# MPU9150_Breakout.net
KiCad netlist of a schematic drawn in EAGLE
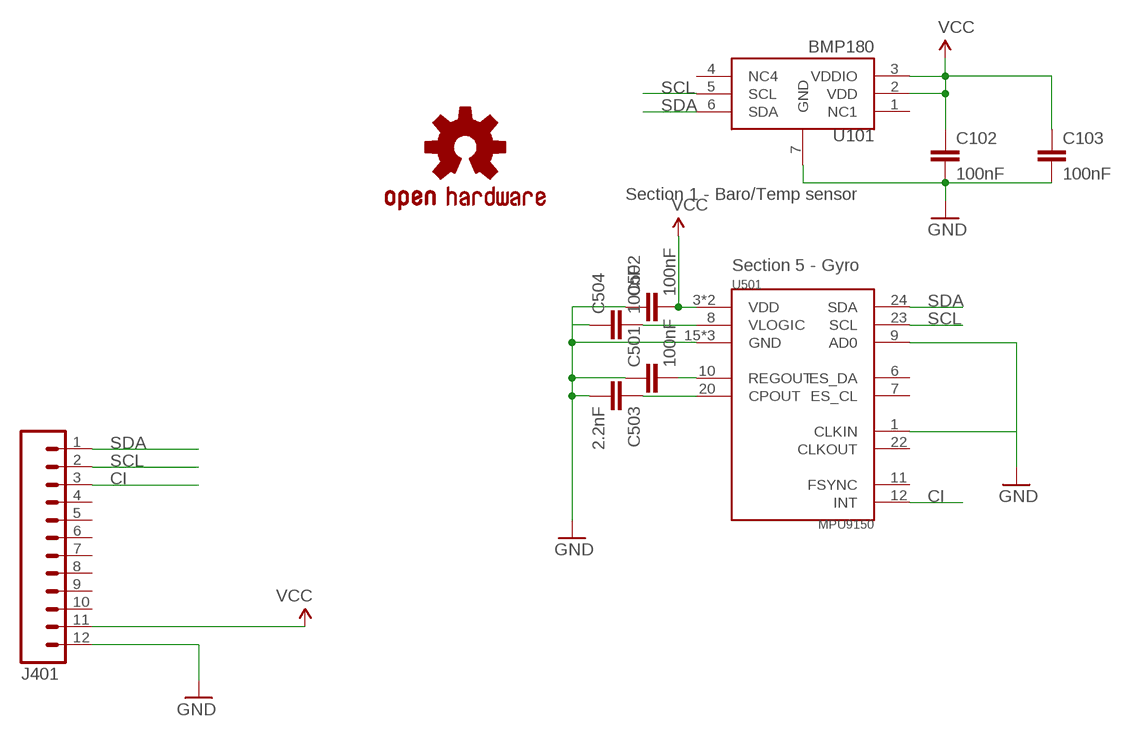
[diagram p0: schematic, sheet 1]

(export (version "E")
  (design (tool "Eeschema 10.0.6"))
  (components
    (comp (ref "C102")
      (value "100nF")
      (footprint "eagle-import:0603-CAP")
      (libsource (lib "eagle-import") (part "CAP0603-CAP"))
    )
    (comp (ref "C103")
      (value "100nF")
      (footprint "eagle-import:0603-CAP")
      (libsource (lib "eagle-import") (part "CAP0603-CAP"))
    )
    (comp (ref "C501")
      (value "100nF")
      (footprint "eagle-import:0603-CAP")
      (libsource (lib "eagle-import") (part "CAP0603-CAP"))
    )
    (comp (ref "C502")
      (value "100nF")
      (footprint "eagle-import:0603-CAP")
      (libsource (lib "eagle-import") (part "CAP0603-CAP"))
    )
    (comp (ref "C503")
      (value "2.2nF")
      (footprint "eagle-import:0603-CAP")
      (libsource (lib "eagle-import") (part "CAP0603-CAP"))
    )
    (comp (ref "C504")
      (value "100nF")
      (footprint "eagle-import:0603-CAP")
      (libsource (lib "eagle-import") (part "CAP0603-CAP"))
    )
    (comp (ref "J401")
      (value "M12PTH")
      (footprint "eagle-import:1X12")
      (libsource (lib "eagle-import") (part "M12PTH"))
    )
    (comp (ref "U$2")
      (value "OSHW-LOGOS")
      (footprint "eagle-import:OSHW-LOGO-S")
      (libsource (lib "eagle-import") (part "OSHW-LOGOS"))
    )
    (comp (ref "U101")
      (value "BMP180")
      (footprint "eagle-import:BMP180")
      (libsource (lib "eagle-import") (part "BMP180"))
    )
    (comp (ref "U501")
      (value "MPU9150")
      (footprint "eagle-import:LLGA24")
      (libsource (lib "eagle-import") (part "MPU9150"))
    )
  )
  (nets
    (net (code "1") (name "/CI") (class "Default")
      (node (ref "J401") (pin "3") (pinfunction "3_3") (pintype "passive"))
      (node (ref "U501") (pin "12") (pinfunction "INT_12") (pintype "bidirectional"))
    )
    (net (code "2") (name "/SCL") (class "Default")
      (node (ref "J401") (pin "2") (pinfunction "2_2") (pintype "passive"))
      (node (ref "U101") (pin "5") (pinfunction "SCL_5") (pintype "input"))
      (node (ref "U501") (pin "23") (pinfunction "SCL_23") (pintype "bidirectional"))
    )
    (net (code "3") (name "/SDA") (class "Default")
      (node (ref "J401") (pin "1") (pinfunction "1_1") (pintype "passive"))
      (node (ref "U101") (pin "6") (pinfunction "SDA_6") (pintype "bidirectional"))
      (node (ref "U501") (pin "24") (pinfunction "SDA_24") (pintype "bidirectional"))
    )
    (net (code "4") (name "GND") (class "Default")
      (node (ref "C102") (pin "2") (pinfunction "2_2") (pintype "passive"))
      (node (ref "C103") (pin "2") (pinfunction "2_2") (pintype "passive"))
      (node (ref "C501") (pin "1") (pinfunction "1_1") (pintype "passive"))
      (node (ref "C502") (pin "1") (pinfunction "1_1") (pintype "passive"))
      (node (ref "C503") (pin "2") (pinfunction "2_2") (pintype "passive"))
      (node (ref "C504") (pin "1") (pinfunction "1_1") (pintype "passive"))
      (node (ref "J401") (pin "12") (pinfunction "12_12") (pintype "passive"))
      (node (ref "U101") (pin "7") (pinfunction "GND_7") (pintype "power_in"))
      (node (ref "U501") (pin "1") (pinfunction "CLKIN_1") (pintype "bidirectional"))
      (node (ref "U501") (pin "15") (pinfunction "GND_15") (pintype "bidirectional"))
      (node (ref "U501") (pin "17") (pinfunction "GND_17") (pintype "bidirectional"))
      (node (ref "U501") (pin "18") (pinfunction "GND_18") (pintype "bidirectional"))
      (node (ref "U501") (pin "9") (pinfunction "AD0_9") (pintype "bidirectional"))
    )
    (net (code "5") (name "Net-(U501-CPOUT)") (class "Default")
      (node (ref "C503") (pin "1") (pinfunction "1_1") (pintype "passive"))
      (node (ref "U501") (pin "20") (pinfunction "CPOUT_20") (pintype "bidirectional"))
    )
    (net (code "6") (name "Net-(U501-REGOUT)") (class "Default")
      (node (ref "C501") (pin "2") (pinfunction "2_2") (pintype "passive"))
      (node (ref "U501") (pin "10") (pinfunction "REGOUT_10") (pintype "bidirectional"))
    )
    (net (code "7") (name "Net-(U501-VLOGIC)") (class "Default")
      (node (ref "C504") (pin "2") (pinfunction "2_2") (pintype "passive"))
      (node (ref "U501") (pin "8") (pinfunction "VLOGIC_8") (pintype "bidirectional"))
    )
    (net (code "8") (name "VCC") (class "Default")
      (node (ref "C102") (pin "1") (pinfunction "1_1") (pintype "passive"))
      (node (ref "C103") (pin "1") (pinfunction "1_1") (pintype "passive"))
      (node (ref "C502") (pin "2") (pinfunction "2_2") (pintype "passive"))
      (node (ref "J401") (pin "11") (pinfunction "11_11") (pintype "passive"))
      (node (ref "U101") (pin "2") (pinfunction "VDD_2") (pintype "power_in"))
      (node (ref "U101") (pin "3") (pinfunction "VDDIO_3") (pintype "power_in"))
      (node (ref "U501") (pin "13") (pinfunction "VDD_13") (pintype "bidirectional"))
      (node (ref "U501") (pin "3") (pinfunction "VDD_3") (pintype "bidirectional"))
    )
    (net (code "9") (name "unconnected-(J401-Pad4)") (class "Default")
      (node (ref "J401") (pin "4") (pinfunction "4_4") (pintype "passive"))
    )
    (net (code "10") (name "unconnected-(J401-Pad5)") (class "Default")
      (node (ref "J401") (pin "5") (pinfunction "5_5") (pintype "passive"))
    )
    (net (code "11") (name "unconnected-(J401-Pad6)") (class "Default")
      (node (ref "J401") (pin "6") (pinfunction "6_6") (pintype "passive"))
    )
    (net (code "12") (name "unconnected-(J401-Pad7)") (class "Default")
      (node (ref "J401") (pin "7") (pinfunction "7_7") (pintype "passive"))
    )
    (net (code "13") (name "unconnected-(J401-Pad8)") (class "Default")
      (node (ref "J401") (pin "8") (pinfunction "8_8") (pintype "passive"))
    )
    (net (code "14") (name "unconnected-(J401-Pad9)") (class "Default")
      (node (ref "J401") (pin "9") (pinfunction "9_9") (pintype "passive"))
    )
    (net (code "15") (name "unconnected-(J401-Pad10)") (class "Default")
      (node (ref "J401") (pin "10") (pinfunction "10_10") (pintype "passive"))
    )
    (net (code "16") (name "unconnected-(U101-NC1-Pad1)") (class "Default")
      (node (ref "U101") (pin "1") (pinfunction "NC1_1") (pintype "no_connect"))
    )
    (net (code "17") (name "unconnected-(U101-NC4-Pad4)") (class "Default")
      (node (ref "U101") (pin "4") (pinfunction "NC4_4") (pintype "no_connect"))
    )
    (net (code "18") (name "unconnected-(U501-CLKOUT-Pad22)") (class "Default")
      (node (ref "U501") (pin "22") (pinfunction "CLKOUT_22") (pintype "bidirectional"))
    )
    (net (code "19") (name "unconnected-(U501-ES_CL-Pad7)") (class "Default")
      (node (ref "U501") (pin "7") (pinfunction "ES_CL_7") (pintype "bidirectional"))
    )
    (net (code "20") (name "unconnected-(U501-ES_DA-Pad6)") (class "Default")
      (node (ref "U501") (pin "6") (pinfunction "ES_DA_6") (pintype "bidirectional"))
    )
    (net (code "21") (name "unconnected-(U501-FSYNC-Pad11)") (class "Default")
      (node (ref "U501") (pin "11") (pinfunction "FSYNC_11") (pintype "bidirectional"))
    )
  )
)
